# APD_Design.net
KiCad netlist of a schematic drawn in Altium Designer
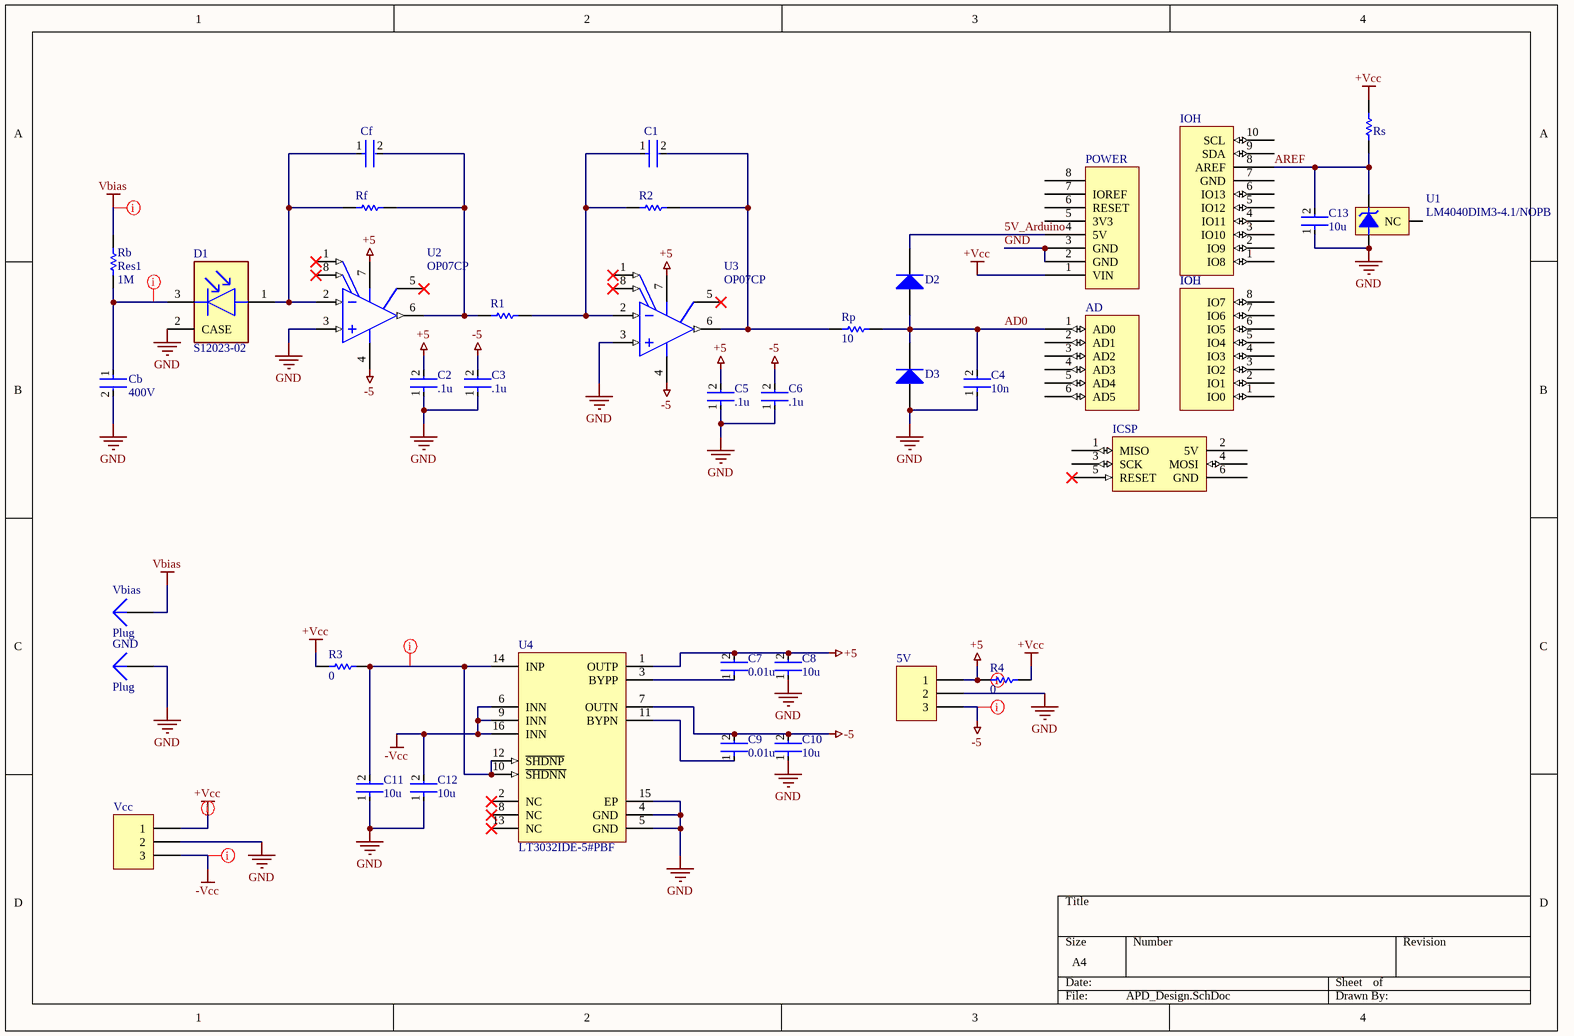
[diagram p0: APD_Design.SchDoc]

(export (version "E")
  (design (tool "Eeschema 10.0.6"))
  (components
    (comp (ref "5V")
      (value "5V")
      (footprint "HDR1X3")
      (description "Header, 3-Pin")
      (fields (field (name "PUBLISHER") "Altium Limited"))
      (libsource (lib "Miscellaneous Connectors") (part "Header 3"))
    )
    (comp (ref "AD")
      (value "AD")
      (footprint "Header:Header 6x1 8.5mm")
      (libsource (lib "Header") (part "AD"))
    )
    (comp (ref "C1")
      (value "~")
      (footprint "FP-C0805C-DG-MFG")
      (description "CAP CER 10UF 10V X5R 0805")
      (fields (field (name "TOLERANCE") "10%") (field (name "MANUFACTURER PART NUMBER") "C0805C106K8PACTU"))
      (libsource (lib "Altium Content Vault") (part "11868f565c42a9108669ba33697ecf6"))
    )
    (comp (ref "C2")
      (value ".1u")
      (footprint "FP-C0805C-DG-MFG")
      (description "CAP CER 10UF 10V X5R 0805")
      (fields (field (name "TOLERANCE") "10%") (field (name "MANUFACTURER PART NUMBER") "C0805C106K8PACTU"))
      (libsource (lib "Altium Content Vault") (part "11868f565c42a9108669ba33697ecf6"))
    )
    (comp (ref "C3")
      (value ".1u")
      (footprint "FP-C0805C-DG-MFG")
      (description "CAP CER 10UF 10V X5R 0805")
      (fields (field (name "TOLERANCE") "10%") (field (name "MANUFACTURER PART NUMBER") "C0805C106K8PACTU"))
      (libsource (lib "Altium Content Vault") (part "11868f565c42a9108669ba33697ecf6"))
    )
    (comp (ref "C4")
      (value "10n")
      (footprint "FP-C0805C-DG-MFG")
      (description "CAP CER 10UF 10V X5R 0805")
      (fields (field (name "TOLERANCE") "10%") (field (name "MANUFACTURER PART NUMBER") "C0805C106K8PACTU"))
      (libsource (lib "Altium Content Vault") (part "11868f565c42a9108669ba33697ecf6"))
    )
    (comp (ref "C5")
      (value ".1u")
      (footprint "FP-C0805C-DG-MFG")
      (description "CAP CER 10UF 10V X5R 0805")
      (fields (field (name "TOLERANCE") "10%") (field (name "MANUFACTURER PART NUMBER") "C0805C106K8PACTU"))
      (libsource (lib "Altium Content Vault") (part "11868f565c42a9108669ba33697ecf6"))
    )
    (comp (ref "C6")
      (value ".1u")
      (footprint "FP-C0805C-DG-MFG")
      (description "CAP CER 10UF 10V X5R 0805")
      (fields (field (name "TOLERANCE") "10%") (field (name "MANUFACTURER PART NUMBER") "C0805C106K8PACTU"))
      (libsource (lib "Altium Content Vault") (part "11868f565c42a9108669ba33697ecf6"))
    )
    (comp (ref "C7")
      (value "0.01u")
      (footprint "FP-C0805C-DG-MFG")
      (description "CAP CER 10UF 10V X5R 0805")
      (fields (field (name "TOLERANCE") "10%") (field (name "MANUFACTURER PART NUMBER") "C0805C106K8PACTU"))
      (libsource (lib "Altium Content Vault") (part "11868f565c42a9108669ba33697ecf6"))
    )
    (comp (ref "C8")
      (value "10u")
      (footprint "FP-C0805C-DG-MFG")
      (description "CAP CER 10UF 10V X5R 0805")
      (fields (field (name "TOLERANCE") "10%") (field (name "MANUFACTURER PART NUMBER") "C0805C106K8PACTU"))
      (libsource (lib "Altium Content Vault") (part "11868f565c42a9108669ba33697ecf6"))
    )
    (comp (ref "C9")
      (value "0.01u")
      (footprint "FP-C0805C-DG-MFG")
      (description "CAP CER 10UF 10V X5R 0805")
      (fields (field (name "TOLERANCE") "10%") (field (name "MANUFACTURER PART NUMBER") "C0805C106K8PACTU"))
      (libsource (lib "Altium Content Vault") (part "11868f565c42a9108669ba33697ecf6"))
    )
    (comp (ref "C10")
      (value "10u")
      (footprint "FP-C0805C-DG-MFG")
      (description "CAP CER 10UF 10V X5R 0805")
      (fields (field (name "TOLERANCE") "10%") (field (name "MANUFACTURER PART NUMBER") "C0805C106K8PACTU"))
      (libsource (lib "Altium Content Vault") (part "11868f565c42a9108669ba33697ecf6"))
    )
    (comp (ref "C11")
      (value "10u")
      (footprint "FP-C0805C-DG-MFG")
      (description "CAP CER 10UF 10V X5R 0805")
      (fields (field (name "TOLERANCE") "10%") (field (name "MANUFACTURER PART NUMBER") "C0805C106K8PACTU"))
      (libsource (lib "Altium Content Vault") (part "11868f565c42a9108669ba33697ecf6"))
    )
    (comp (ref "C12")
      (value "10u")
      (footprint "FP-C0805C-DG-MFG")
      (description "CAP CER 10UF 10V X5R 0805")
      (fields (field (name "TOLERANCE") "10%") (field (name "MANUFACTURER PART NUMBER") "C0805C106K8PACTU"))
      (libsource (lib "Altium Content Vault") (part "11868f565c42a9108669ba33697ecf6"))
    )
    (comp (ref "C13")
      (value "10u")
      (footprint "FP-C0805C-DG-MFG")
      (description "CAP CER 10UF 10V X5R 0805")
      (fields (field (name "TOLERANCE") "10%") (field (name "MANUFACTURER PART NUMBER") "C0805C106K8PACTU"))
      (libsource (lib "Altium Content Vault") (part "11868f565c42a9108669ba33697ecf6"))
    )
    (comp (ref "Cb")
      (value "400V")
      (footprint "FP-VY1472M63Y5UQ6TV0-MFG")
      (description "CAP CER 4700PF 760VAC Y5U RADIAL")
      (fields (field (name "TOLERANCE") "20%") (field (name "VOLTAGE") "500V"))
      (libsource (lib "Altium Content Vault") (part "11868f565c42a9108669ba33697ecf6"))
    )
    (comp (ref "Cf")
      (value "~")
      (footprint "FP-C0805C-DG-MFG")
      (description "CAP CER 10UF 10V X5R 0805")
      (fields (field (name "TOLERANCE") "10%") (field (name "MANUFACTURER PART NUMBER") "C0805C106K8PACTU"))
      (libsource (lib "Altium Content Vault") (part "11868f565c42a9108669ba33697ecf6"))
    )
    (comp (ref "D1")
      (value "S12023-02")
      (footprint "FP-S12023-02-MFG")
      (description "IR-photodiode Package: TO-18 Wavelength of max. photosensitivity: 800 nm")
      (libsource (lib "Altium Content Vault") (part "17faf3f6058c1f9699b1d9e7a9e4ed2"))
    )
    (comp (ref "D2")
      (value "Diode 1N4148")
      (footprint "DO-35")
      (description "High Conductance Fast Diode")
      (fields (field (name "PUBLISHER") "Altium Limited"))
      (libsource (lib "Miscellaneous Devices") (part "Diode 1N4148"))
    )
    (comp (ref "D3")
      (value "Diode 1N4148")
      (footprint "DO-35")
      (description "High Conductance Fast Diode")
      (fields (field (name "PUBLISHER") "Altium Limited"))
      (libsource (lib "Miscellaneous Devices") (part "Diode 1N4148"))
    )
    (comp (ref "GND")
      (value "Plug")
      (footprint "PIN1")
      (fields (field (name "PUBLISHER") "Altium Limited"))
      (libsource (lib "Miscellaneous Connectors") (part "Plug"))
    )
    (comp (ref "ICSP") (value "ICSP") (footprint "ICSP") (libsource (lib "Header") (part "ICSP")))
    (comp (ref "IOH")
      (value "IOH")
      (footprint "Header:Header 10x1 8.5mm")
      (libsource (lib "Header") (part "IOH"))
    )
    (comp (ref "IOL") (value "IOL") (footprint "Header 8x1 8.5mm") (libsource (lib "Header") (part "IOL")))
    (comp (ref "POWER")
      (value "POWER_UNO")
      (footprint "Header 8x1 8.5mm")
      (libsource (lib "Header") (part "POWER_UNO"))
    )
    (comp (ref "R1")
      (value "CRCW08050000Z0EA")
      (footprint "RESC2013X50X30LL20T20")
      (fields (field (name "MANUFACTURER") "Vishay Dale"))
      (libsource (lib "Altium Content Vault") (part "RES"))
    )
    (comp (ref "R2")
      (value "CRCW08050000Z0EA")
      (footprint "RESC2013X50X30LL20T20")
      (fields (field (name "MANUFACTURER") "Vishay Dale"))
      (libsource (lib "Altium Content Vault") (part "RES"))
    )
    (comp (ref "R3")
      (value "0")
      (footprint "RESC2013X50X30LL20T20")
      (fields (field (name "MANUFACTURER") "Vishay Dale") (field (name "PART NUMBER") "CRCW08050000Z0EA"))
      (libsource (lib "Altium Content Vault") (part "RES"))
    )
    (comp (ref "R4")
      (value "0")
      (footprint "RESC2013X50X30LL20T20")
      (fields (field (name "MANUFACTURER") "Vishay Dale") (field (name "PART NUMBER") "CRCW08050000Z0EA"))
      (libsource (lib "Altium Content Vault") (part "RES"))
    )
    (comp (ref "Rb")
      (value "Res1")
      (footprint "AXIAL-0.3")
      (description "Resistor")
      (fields (field (name "ALTIUM_VALUE") "1M") (field (name "PUBLISHER") "Altium Limited"))
      (libsource (lib "Miscellaneous Devices") (part "Res1"))
    )
    (comp (ref "Rf")
      (value "~")
      (footprint "RESC2013X50X30LL20T20")
      (fields (field (name "MANUFACTURER") "Vishay Dale") (field (name "PART NUMBER") "CRCW08050000Z0EA"))
      (libsource (lib "Altium Content Vault") (part "RES"))
    )
    (comp (ref "Rp")
      (value "10")
      (footprint "RESC2013X50X30LL20T20")
      (fields (field (name "MANUFACTURER") "Vishay Dale") (field (name "PART NUMBER") "CRCW08050000Z0EA"))
      (libsource (lib "Altium Content Vault") (part "RES"))
    )
    (comp (ref "Rs")
      (value "CRCW08050000Z0EA")
      (footprint "RESC2013X50X30LL20T20")
      (fields (field (name "MANUFACTURER") "Vishay Dale"))
      (libsource (lib "Altium Content Vault") (part "RES"))
    )
    (comp (ref "U1")
      (value "LM4040DIM3-4.1/NOPB")
      (footprint "MF03A_N")
      (description "Precision Micropower Shunt Voltage Reference, 3-pin SOT-23, Pb-Free")
      (fields (field (name "MANUFACTURER") "National Semiconductor"))
      (libsource (lib "Altium Content Vault") (part "PM-REF-LM4040-SOT3"))
    )
    (comp (ref "U2")
      (value "OP07CP")
      (footprint "P0008A")
      (description "Low-Offset Voltage Operational Amplifier, 6 to 36 V, 0 to 70 degC, 8-pin DIP (P8), Pb-Free (RoHS)")
      (fields (field (name "MANUFACTURER") "Texas Instruments"))
      (libsource (lib "Altium Content Vault") (part "TI-OP07X-X8"))
    )
    (comp (ref "U3")
      (value "OP07CP")
      (footprint "P0008A")
      (description "Low-Offset Voltage Operational Amplifier, 6 to 36 V, 0 to 70 degC, 8-pin DIP (P8), Pb-Free (RoHS)")
      (fields (field (name "MANUFACTURER") "Texas Instruments"))
      (libsource (lib "Altium Content Vault") (part "TI-OP07X-X8"))
    )
    (comp (ref "U4")
      (value "LT3032IDE-5#PBF")
      (footprint "LT-DE14MA-14_V")
      (fields (field (name "MANUFACTURER") "Linear Technology"))
      (libsource (lib "Altium Content Vault") (part "LT-LT3032-DE14MA-14"))
    )
    (comp (ref "Vbias")
      (value "Plug")
      (footprint "PIN1")
      (fields (field (name "PUBLISHER") "Altium Limited"))
      (libsource (lib "Miscellaneous Connectors") (part "Plug"))
    )
    (comp (ref "Vcc")
      (value "Vcc")
      (footprint "HDR1X3")
      (description "Header, 3-Pin")
      (fields (field (name "PUBLISHER") "Altium Limited"))
      (libsource (lib "Miscellaneous Connectors") (part "Header 3"))
    )
  )
  (nets
    (net (code "1") (name "+5") (class "Default")
      (node (ref "5V") (pin "1") (pinfunction "1_1") (pintype "passive"))
      (node (ref "C2") (pin "2") (pinfunction "2_2") (pintype "passive"))
      (node (ref "C5") (pin "2") (pinfunction "2_2") (pintype "passive"))
      (node (ref "C7") (pin "2") (pinfunction "2_2") (pintype "passive"))
      (node (ref "C8") (pin "2") (pinfunction "2_2") (pintype "passive"))
      (node (ref "R4") (pin "1") (pinfunction "1_1") (pintype "passive"))
      (node (ref "U2") (pin "7") (pinfunction "VCC+_7") (pintype "power_in"))
      (node (ref "U3") (pin "7") (pinfunction "VCC+_7") (pintype "power_in"))
      (node (ref "U4") (pin "1") (pinfunction "OUTP_1") (pintype "power_in"))
    )
    (net (code "2") (name "+Vcc") (class "Default")
      (node (ref "POWER") (pin "1") (pinfunction "VIN_1") (pintype "power_in"))
      (node (ref "R3") (pin "1") (pinfunction "1_1") (pintype "passive"))
      (node (ref "R4") (pin "2") (pinfunction "2_2") (pintype "passive"))
      (node (ref "Rs") (pin "2") (pinfunction "2_2") (pintype "passive"))
      (node (ref "Vcc") (pin "1") (pinfunction "1_1") (pintype "passive"))
    )
    (net (code "3") (name "-5") (class "Default")
      (node (ref "5V") (pin "3") (pinfunction "3_3") (pintype "passive"))
      (node (ref "C10") (pin "2") (pinfunction "2_2") (pintype "passive"))
      (node (ref "C3") (pin "2") (pinfunction "2_2") (pintype "passive"))
      (node (ref "C6") (pin "2") (pinfunction "2_2") (pintype "passive"))
      (node (ref "C9") (pin "2") (pinfunction "2_2") (pintype "passive"))
      (node (ref "U2") (pin "4") (pinfunction "VCC-_4") (pintype "power_in"))
      (node (ref "U3") (pin "4") (pinfunction "VCC-_4") (pintype "power_in"))
      (node (ref "U4") (pin "7") (pinfunction "OUTN_7") (pintype "power_in"))
    )
    (net (code "4") (name "-Vcc") (class "Default")
      (node (ref "C12") (pin "2") (pinfunction "2_2") (pintype "passive"))
      (node (ref "U4") (pin "16") (pinfunction "INN_16") (pintype "power_in"))
      (node (ref "U4") (pin "6") (pinfunction "INN_6") (pintype "power_in"))
      (node (ref "U4") (pin "9") (pinfunction "INN_9") (pintype "power_in"))
      (node (ref "Vcc") (pin "3") (pinfunction "3_3") (pintype "passive"))
    )
    (net (code "5") (name "/5V_Arduino") (class "Default")
      (node (ref "D2") (pin "2") (pinfunction "K_2") (pintype "passive"))
      (node (ref "POWER") (pin "4") (pinfunction "5V_4") (pintype "power_in"))
    )
    (net (code "6") (name "/AD0") (class "Default")
      (node (ref "AD") (pin "1") (pinfunction "AD0_1") (pintype "bidirectional"))
      (node (ref "C4") (pin "2") (pinfunction "2_2") (pintype "passive"))
      (node (ref "D2") (pin "1") (pinfunction "A_1") (pintype "passive"))
      (node (ref "D3") (pin "2") (pinfunction "K_2") (pintype "passive"))
      (node (ref "Rp") (pin "2") (pinfunction "2_2") (pintype "passive"))
    )
    (net (code "7") (name "/AREF") (class "Default")
      (node (ref "C13") (pin "2") (pinfunction "2_2") (pintype "passive"))
      (node (ref "IOH") (pin "8") (pinfunction "AREF_8") (pintype "passive"))
      (node (ref "Rs") (pin "1") (pinfunction "1_1") (pintype "passive"))
      (node (ref "U1") (pin "1") (pinfunction "+V_1") (pintype "passive"))
    )
    (net (code "8") (name "GND") (class "Default")
      (node (ref "5V") (pin "2") (pinfunction "2_2") (pintype "passive"))
      (node (ref "C10") (pin "1") (pinfunction "1_1") (pintype "passive"))
      (node (ref "C11") (pin "1") (pinfunction "1_1") (pintype "passive"))
      (node (ref "C12") (pin "1") (pinfunction "1_1") (pintype "passive"))
      (node (ref "C13") (pin "1") (pinfunction "1_1") (pintype "passive"))
      (node (ref "C2") (pin "1") (pinfunction "1_1") (pintype "passive"))
      (node (ref "C3") (pin "1") (pinfunction "1_1") (pintype "passive"))
      (node (ref "C4") (pin "1") (pinfunction "1_1") (pintype "passive"))
      (node (ref "C5") (pin "1") (pinfunction "1_1") (pintype "passive"))
      (node (ref "C6") (pin "1") (pinfunction "1_1") (pintype "passive"))
      (node (ref "C8") (pin "1") (pinfunction "1_1") (pintype "passive"))
      (node (ref "Cb") (pin "2") (pinfunction "2_2") (pintype "passive"))
      (node (ref "D1") (pin "2") (pinfunction "CASE_2") (pintype "passive"))
      (node (ref "D3") (pin "1") (pinfunction "A_1") (pintype "passive"))
      (node (ref "GND") (pin "1") (pinfunction "1_1") (pintype "passive"))
      (node (ref "POWER") (pin "2") (pinfunction "GND_2") (pintype "power_in"))
      (node (ref "POWER") (pin "3") (pinfunction "GND_3") (pintype "power_in"))
      (node (ref "U1") (pin "2") (pinfunction "-V_2") (pintype "passive"))
      (node (ref "U2") (pin "3") (pinfunction "IN+_3") (pintype "input"))
      (node (ref "U3") (pin "3") (pinfunction "IN+_3") (pintype "input"))
      (node (ref "U4") (pin "15") (pinfunction "EP_15") (pintype "power_in"))
      (node (ref "U4") (pin "4") (pinfunction "GND_4") (pintype "power_in"))
      (node (ref "U4") (pin "5") (pinfunction "GND_5") (pintype "power_in"))
      (node (ref "Vcc") (pin "2") (pinfunction "2_2") (pintype "passive"))
    )
    (net (code "9") (name "Net-(D1-A)") (class "Default")
      (node (ref "Cf") (pin "1") (pinfunction "1_1") (pintype "passive"))
      (node (ref "D1") (pin "1") (pinfunction "A_1") (pintype "passive"))
      (node (ref "Rf") (pin "1") (pinfunction "1_1") (pintype "passive"))
      (node (ref "U2") (pin "2") (pinfunction "IN-_2") (pintype "input"))
    )
    (net (code "10") (name "Net-(D1-C)") (class "Default")
      (node (ref "Cb") (pin "1") (pinfunction "1_1") (pintype "passive"))
      (node (ref "D1") (pin "3") (pinfunction "C_3") (pintype "passive"))
      (node (ref "Rb") (pin "1") (pinfunction "1_1") (pintype "passive"))
    )
    (net (code "11") (name "Net-(U2-OUT)") (class "Default")
      (node (ref "Cf") (pin "2") (pinfunction "2_2") (pintype "passive"))
      (node (ref "R1") (pin "1") (pinfunction "1_1") (pintype "passive"))
      (node (ref "Rf") (pin "2") (pinfunction "2_2") (pintype "passive"))
      (node (ref "U2") (pin "6") (pinfunction "OUT_6") (pintype "output"))
    )
    (net (code "12") (name "Net-(U3-IN-)") (class "Default")
      (node (ref "C1") (pin "1") (pinfunction "1_1") (pintype "passive"))
      (node (ref "R1") (pin "2") (pinfunction "2_2") (pintype "passive"))
      (node (ref "R2") (pin "1") (pinfunction "1_1") (pintype "passive"))
      (node (ref "U3") (pin "2") (pinfunction "IN-_2") (pintype "input"))
    )
    (net (code "13") (name "Net-(U3-OUT)") (class "Default")
      (node (ref "C1") (pin "2") (pinfunction "2_2") (pintype "passive"))
      (node (ref "R2") (pin "2") (pinfunction "2_2") (pintype "passive"))
      (node (ref "Rp") (pin "1") (pinfunction "1_1") (pintype "passive"))
      (node (ref "U3") (pin "6") (pinfunction "OUT_6") (pintype "output"))
    )
    (net (code "14") (name "Net-(U4-BYPN)") (class "Default")
      (node (ref "C9") (pin "1") (pinfunction "1_1") (pintype "passive"))
      (node (ref "U4") (pin "11") (pinfunction "BYPN_11") (pintype "passive"))
    )
    (net (code "15") (name "Net-(U4-BYPP)") (class "Default")
      (node (ref "C7") (pin "1") (pinfunction "1_1") (pintype "passive"))
      (node (ref "U4") (pin "3") (pinfunction "BYPP_3") (pintype "passive"))
    )
    (net (code "16") (name "Net-(U4-INP)") (class "Default")
      (node (ref "C11") (pin "2") (pinfunction "2_2") (pintype "passive"))
      (node (ref "R3") (pin "2") (pinfunction "2_2") (pintype "passive"))
      (node (ref "U4") (pin "10") (pinfunction "~{SHDNN}_10") (pintype "input"))
      (node (ref "U4") (pin "12") (pinfunction "~{SHDNP}_12") (pintype "input"))
      (node (ref "U4") (pin "14") (pinfunction "INP_14") (pintype "power_in"))
    )
    (net (code "17") (name "Vbias") (class "Default")
      (node (ref "Rb") (pin "2") (pinfunction "2_2") (pintype "passive"))
      (node (ref "Vbias") (pin "1") (pinfunction "1_1") (pintype "passive"))
    )
    (net (code "18") (name "unconnected-(AD-AD1-Pad2)") (class "Default")
      (node (ref "AD") (pin "2") (pinfunction "AD1_2") (pintype "bidirectional"))
    )
    (net (code "19") (name "unconnected-(AD-AD2-Pad3)") (class "Default")
      (node (ref "AD") (pin "3") (pinfunction "AD2_3") (pintype "bidirectional"))
    )
    (net (code "20") (name "unconnected-(AD-AD3-Pad4)") (class "Default")
      (node (ref "AD") (pin "4") (pinfunction "AD3_4") (pintype "bidirectional"))
    )
    (net (code "21") (name "unconnected-(AD-AD4-Pad5)") (class "Default")
      (node (ref "AD") (pin "5") (pinfunction "AD4_5") (pintype "bidirectional"))
    )
    (net (code "22") (name "unconnected-(AD-AD5-Pad6)") (class "Default")
      (node (ref "AD") (pin "6") (pinfunction "AD5_6") (pintype "bidirectional"))
    )
    (net (code "23") (name "unconnected-(ICSP-5V-Pad2)") (class "Default")
      (node (ref "ICSP") (pin "2") (pinfunction "5V_2") (pintype "power_in"))
    )
    (net (code "24") (name "unconnected-(ICSP-GND-Pad6)") (class "Default")
      (node (ref "ICSP") (pin "6") (pinfunction "GND_6") (pintype "power_in"))
    )
    (net (code "25") (name "unconnected-(ICSP-MISO-Pad1)") (class "Default")
      (node (ref "ICSP") (pin "1") (pinfunction "MISO_1") (pintype "bidirectional"))
    )
    (net (code "26") (name "unconnected-(ICSP-MOSI-Pad4)") (class "Default")
      (node (ref "ICSP") (pin "4") (pinfunction "MOSI_4") (pintype "bidirectional"))
    )
    (net (code "27") (name "unconnected-(ICSP-RESET-Pad5)") (class "Default")
      (node (ref "ICSP") (pin "5") (pinfunction "RESET_5") (pintype "input+no_connect"))
    )
    (net (code "28") (name "unconnected-(ICSP-SCK-Pad3)") (class "Default")
      (node (ref "ICSP") (pin "3") (pinfunction "SCK_3") (pintype "bidirectional"))
    )
    (net (code "29") (name "unconnected-(IOH-GND-Pad7)") (class "Default")
      (node (ref "IOH") (pin "7") (pinfunction "GND_7") (pintype "power_in"))
    )
    (net (code "30") (name "unconnected-(IOH-IO8-Pad1)") (class "Default")
      (node (ref "IOH") (pin "1") (pinfunction "IO8_1") (pintype "bidirectional"))
    )
    (net (code "31") (name "unconnected-(IOH-IO9-Pad2)") (class "Default")
      (node (ref "IOH") (pin "2") (pinfunction "IO9_2") (pintype "bidirectional"))
    )
    (net (code "32") (name "unconnected-(IOH-IO10-Pad3)") (class "Default")
      (node (ref "IOH") (pin "3") (pinfunction "IO10_3") (pintype "bidirectional"))
    )
    (net (code "33") (name "unconnected-(IOH-IO11-Pad4)") (class "Default")
      (node (ref "IOH") (pin "4") (pinfunction "IO11_4") (pintype "bidirectional"))
    )
    (net (code "34") (name "unconnected-(IOH-IO12-Pad5)") (class "Default")
      (node (ref "IOH") (pin "5") (pinfunction "IO12_5") (pintype "bidirectional"))
    )
    (net (code "35") (name "unconnected-(IOH-IO13-Pad6)") (class "Default")
      (node (ref "IOH") (pin "6") (pinfunction "IO13_6") (pintype "bidirectional"))
    )
    (net (code "36") (name "unconnected-(IOH-SCL-Pad10)") (class "Default")
      (node (ref "IOH") (pin "10") (pinfunction "SCL_10") (pintype "bidirectional"))
    )
    (net (code "37") (name "unconnected-(IOH-SDA-Pad9)") (class "Default")
      (node (ref "IOH") (pin "9") (pinfunction "SDA_9") (pintype "bidirectional"))
    )
    (net (code "38") (name "unconnected-(IOL-IO0-Pad1)") (class "Default")
      (node (ref "IOL") (pin "1") (pinfunction "IO0_1") (pintype "bidirectional"))
    )
    (net (code "39") (name "unconnected-(IOL-IO1-Pad2)") (class "Default")
      (node (ref "IOL") (pin "2") (pinfunction "IO1_2") (pintype "bidirectional"))
    )
    (net (code "40") (name "unconnected-(IOL-IO2-Pad3)") (class "Default")
      (node (ref "IOL") (pin "3") (pinfunction "IO2_3") (pintype "bidirectional"))
    )
    (net (code "41") (name "unconnected-(IOL-IO3-Pad4)") (class "Default")
      (node (ref "IOL") (pin "4") (pinfunction "IO3_4") (pintype "bidirectional"))
    )
    (net (code "42") (name "unconnected-(IOL-IO4-Pad5)") (class "Default")
      (node (ref "IOL") (pin "5") (pinfunction "IO4_5") (pintype "bidirectional"))
    )
    (net (code "43") (name "unconnected-(IOL-IO5-Pad6)") (class "Default")
      (node (ref "IOL") (pin "6") (pinfunction "IO5_6") (pintype "bidirectional"))
    )
    (net (code "44") (name "unconnected-(IOL-IO6-Pad7)") (class "Default")
      (node (ref "IOL") (pin "7") (pinfunction "IO6_7") (pintype "bidirectional"))
    )
    (net (code "45") (name "unconnected-(IOL-IO7-Pad8)") (class "Default")
      (node (ref "IOL") (pin "8") (pinfunction "IO7_8") (pintype "bidirectional"))
    )
    (net (code "46") (name "unconnected-(POWER-3V3-Pad5)") (class "Default")
      (node (ref "POWER") (pin "5") (pinfunction "3V3_5") (pintype "power_in"))
    )
    (net (code "47") (name "unconnected-(POWER-IOREF-Pad7)") (class "Default")
      (node (ref "POWER") (pin "7") (pinfunction "IOREF_7") (pintype "power_in"))
    )
    (net (code "48") (name "unconnected-(POWER-Pad8)") (class "Default")
      (node (ref "POWER") (pin "8") (pintype "passive"))
    )
    (net (code "49") (name "unconnected-(POWER-RESET-Pad6)") (class "Default")
      (node (ref "POWER") (pin "6") (pinfunction "RESET_6") (pintype "passive"))
    )
    (net (code "50") (name "unconnected-(U1-NC-Pad3)") (class "Default")
      (node (ref "U1") (pin "3") (pinfunction "NC_3") (pintype "passive"))
    )
    (net (code "51") (name "unconnected-(U2-NC-Pad5)") (class "Default")
      (node (ref "U2") (pin "5") (pinfunction "NC_5") (pintype "passive+no_connect"))
    )
    (net (code "52") (name "unconnected-(U2-OFFSET_N1-Pad1)") (class "Default")
      (node (ref "U2") (pin "1") (pinfunction "OFFSET_N1_1") (pintype "input+no_connect"))
    )
    (net (code "53") (name "unconnected-(U2-OFFSET_N2-Pad8)") (class "Default")
      (node (ref "U2") (pin "8") (pinfunction "OFFSET_N2_8") (pintype "input+no_connect"))
    )
    (net (code "54") (name "unconnected-(U3-NC-Pad5)") (class "Default")
      (node (ref "U3") (pin "5") (pinfunction "NC_5") (pintype "passive+no_connect"))
    )
    (net (code "55") (name "unconnected-(U3-OFFSET_N1-Pad1)") (class "Default")
      (node (ref "U3") (pin "1") (pinfunction "OFFSET_N1_1") (pintype "input+no_connect"))
    )
    (net (code "56") (name "unconnected-(U3-OFFSET_N2-Pad8)") (class "Default")
      (node (ref "U3") (pin "8") (pinfunction "OFFSET_N2_8") (pintype "input+no_connect"))
    )
    (net (code "57") (name "unconnected-(U4-NC-Pad2)") (class "Default")
      (node (ref "U4") (pin "2") (pinfunction "NC_2") (pintype "passive+no_connect"))
    )
    (net (code "58") (name "unconnected-(U4-NC-Pad8)") (class "Default")
      (node (ref "U4") (pin "8") (pinfunction "NC_8") (pintype "passive+no_connect"))
    )
    (net (code "59") (name "unconnected-(U4-NC-Pad13)") (class "Default")
      (node (ref "U4") (pin "13") (pinfunction "NC_13") (pintype "passive+no_connect"))
    )
  )
)
